# cart.net
KiCad netlist of a schematic drawn in EAGLE
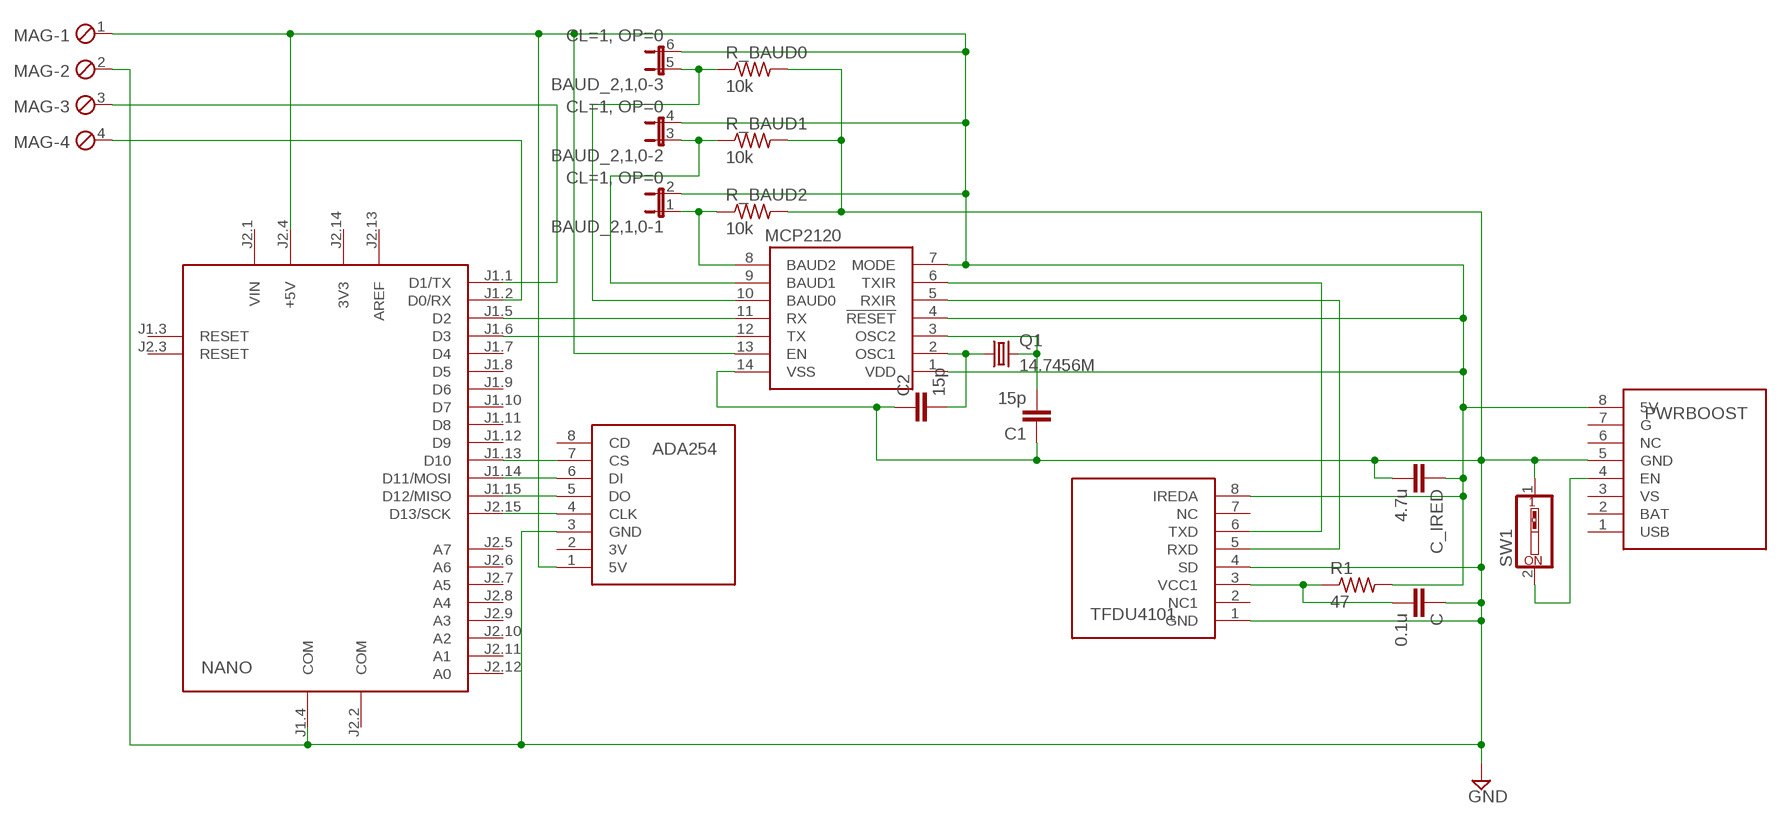
[diagram p0: schematic, sheet 1]

(export (version "E")
  (design (tool "Eeschema 10.0.6"))
  (components
    (comp (ref "ADA254")
      (value "ADA254_SD_READER")
      (footprint "eagle-import:ADA254_SD_READER")
      (libsource (lib "eagle-import") (part "ADA254_SD_READER"))
    )
    (comp (ref "BAUD_2,1,0")
      (value "CL=1, OP=0")
      (footprint "eagle-import:JP3Q")
      (libsource (lib "eagle-import") (part "JP3QE"))
    )
    (comp (ref "C")
      (value "0.1u")
      (footprint "eagle-import:C1206")
      (libsource (lib "eagle-import") (part "C-EUC1206"))
    )
    (comp (ref "C1")
      (value "15p")
      (footprint "eagle-import:C1206")
      (libsource (lib "eagle-import") (part "C-EUC1206"))
    )
    (comp (ref "C2")
      (value "15p")
      (footprint "eagle-import:C1206")
      (libsource (lib "eagle-import") (part "C-EUC1206"))
    )
    (comp (ref "C_IRED")
      (value "4.7u")
      (footprint "eagle-import:C1206")
      (libsource (lib "eagle-import") (part "C-EUC1206"))
    )
    (comp (ref "MAG")
      (value "MPT4")
      (footprint "eagle-import:4POL254")
      (libsource (lib "eagle-import") (part "MPT4"))
    )
    (comp (ref "MCP2120")
      (value "MCP2120_SOIC")
      (footprint "eagle-import:SO14")
      (libsource (lib "eagle-import") (part "MCP2120_SOIC"))
    )
    (comp (ref "NANO")
      (value "ARDUINO_NANO2")
      (footprint "eagle-import:ARDUINO_NANO2")
      (libsource (lib "eagle-import") (part "ARDUINO_NANO2"))
    )
    (comp (ref "PWRBOOST")
      (value "POWERBOOST_1000C")
      (footprint "eagle-import:POWERBOOST_1000C")
      (libsource (lib "eagle-import") (part "POWERBOOST_1000C"))
    )
    (comp (ref "Q1")
      (value "14.7456M")
      (footprint "eagle-import:TC26V")
      (libsource (lib "eagle-import") (part "CRYSTALTC26V"))
    )
    (comp (ref "R1")
      (value "47")
      (footprint "eagle-import:R1206W")
      (libsource (lib "eagle-import") (part "R-US_R1206W"))
    )
    (comp (ref "R_BAUD0")
      (value "10k")
      (footprint "eagle-import:R1206W")
      (libsource (lib "eagle-import") (part "R-US_R1206W"))
    )
    (comp (ref "R_BAUD1")
      (value "10k")
      (footprint "eagle-import:R1206W")
      (libsource (lib "eagle-import") (part "R-US_R1206W"))
    )
    (comp (ref "R_BAUD2")
      (value "10k")
      (footprint "eagle-import:R1206W")
      (libsource (lib "eagle-import") (part "R-US_R1206W"))
    )
    (comp (ref "SW1")
      (value "SW_DIP-1")
      (footprint "eagle-import:EDG-01")
      (libsource (lib "eagle-import") (part "SW_DIP-1"))
    )
    (comp (ref "TFDU4101")
      (value "TFDU4101_SIDE")
      (footprint "eagle-import:TFDU4101_SIDE")
      (libsource (lib "eagle-import") (part "TFDU4101_SIDE"))
    )
  )
  (nets
    (net (code "1") (name "/3V3") (class "Default")
      (node (ref "NANO") (pin "J2.14") (pinfunction "3V3_J2.14") (pintype "power_in"))
    )
    (net (code "2") (name "/AREF") (class "Default")
      (node (ref "NANO") (pin "J2.13") (pinfunction "AREF_J2.13") (pintype "power_in"))
    )
    (net (code "3") (name "/COM") (class "Default")
      (node (ref "NANO") (pin "J2.2") (pinfunction "COM_J2.2") (pintype "power_in"))
    )
    (net (code "4") (name "/VIN") (class "Default")
      (node (ref "NANO") (pin "J2.1") (pinfunction "VIN_J2.1") (pintype "power_in"))
    )
    (net (code "5") (name "GND") (class "Default")
      (node (ref "ADA254") (pin "3") (pinfunction "GND_3") (pintype "bidirectional"))
      (node (ref "C") (pin "1") (pinfunction "1_1") (pintype "passive"))
      (node (ref "C1") (pin "1") (pinfunction "1_1") (pintype "passive"))
      (node (ref "C2") (pin "1") (pinfunction "1_1") (pintype "passive"))
      (node (ref "C_IRED") (pin "2") (pinfunction "2_2") (pintype "passive"))
      (node (ref "MAG") (pin "2") (pinfunction "1_2") (pintype "passive"))
      (node (ref "MCP2120") (pin "14") (pinfunction "VSS_14") (pintype "bidirectional"))
      (node (ref "NANO") (pin "J1.4") (pinfunction "COM_J1.4") (pintype "power_in"))
      (node (ref "PWRBOOST") (pin "5") (pinfunction "GND_5") (pintype "bidirectional"))
      (node (ref "R_BAUD0") (pin "2") (pinfunction "2_2") (pintype "passive"))
      (node (ref "R_BAUD1") (pin "2") (pinfunction "2_2") (pintype "passive"))
      (node (ref "R_BAUD2") (pin "2") (pinfunction "2_2") (pintype "passive"))
      (node (ref "SW1") (pin "1") (pinfunction "1_1") (pintype "passive"))
      (node (ref "TFDU4101") (pin "1") (pinfunction "GND_1") (pintype "bidirectional"))
      (node (ref "TFDU4101") (pin "4") (pinfunction "SD_4") (pintype "bidirectional"))
    )
    (net (code "6") (name "Net-(ADA254-5V)") (class "Default")
      (node (ref "ADA254") (pin "1") (pinfunction "5V_1") (pintype "bidirectional"))
      (node (ref "BAUD_2,1,0") (pin "2") (pinfunction "2_2") (pintype "passive"))
      (node (ref "BAUD_2,1,0") (pin "4") (pinfunction "2_4") (pintype "passive"))
      (node (ref "BAUD_2,1,0") (pin "6") (pinfunction "2_6") (pintype "passive"))
      (node (ref "C_IRED") (pin "1") (pinfunction "1_1") (pintype "passive"))
      (node (ref "MAG") (pin "1") (pinfunction "1_1") (pintype "passive"))
      (node (ref "MCP2120") (pin "1") (pinfunction "VDD_1") (pintype "bidirectional"))
      (node (ref "MCP2120") (pin "13") (pinfunction "EN_13") (pintype "bidirectional"))
      (node (ref "MCP2120") (pin "4") (pinfunction "~{RESET}_4") (pintype "bidirectional"))
      (node (ref "MCP2120") (pin "7") (pinfunction "MODE_7") (pintype "bidirectional"))
      (node (ref "NANO") (pin "J2.4") (pinfunction "+5V_J2.4") (pintype "power_in"))
      (node (ref "PWRBOOST") (pin "8") (pinfunction "5V_8") (pintype "bidirectional"))
      (node (ref "R1") (pin "2") (pinfunction "2_2") (pintype "passive"))
      (node (ref "TFDU4101") (pin "8") (pinfunction "IREDA_8") (pintype "bidirectional"))
    )
    (net (code "7") (name "Net-(ADA254-CLK)") (class "Default")
      (node (ref "ADA254") (pin "4") (pinfunction "CLK_4") (pintype "bidirectional"))
      (node (ref "NANO") (pin "J2.15") (pinfunction "D13/SCK_J2.15") (pintype "bidirectional"))
    )
    (net (code "8") (name "Net-(ADA254-CS)") (class "Default")
      (node (ref "ADA254") (pin "7") (pinfunction "CS_7") (pintype "bidirectional"))
      (node (ref "NANO") (pin "J1.13") (pinfunction "D10_J1.13") (pintype "bidirectional"))
    )
    (net (code "9") (name "Net-(ADA254-DI)") (class "Default")
      (node (ref "ADA254") (pin "6") (pinfunction "DI_6") (pintype "bidirectional"))
      (node (ref "NANO") (pin "J1.14") (pinfunction "D11/MOSI_J1.14") (pintype "bidirectional"))
    )
    (net (code "10") (name "Net-(ADA254-DO)") (class "Default")
      (node (ref "ADA254") (pin "5") (pinfunction "DO_5") (pintype "bidirectional"))
      (node (ref "NANO") (pin "J1.15") (pinfunction "D12/MISO_J1.15") (pintype "bidirectional"))
    )
    (net (code "11") (name "Net-(BAUD_2,1,0B-1)") (class "Default")
      (node (ref "BAUD_2,1,0") (pin "3") (pinfunction "1_3") (pintype "passive"))
      (node (ref "MCP2120") (pin "9") (pinfunction "BAUD1_9") (pintype "bidirectional"))
      (node (ref "R_BAUD1") (pin "1") (pinfunction "1_1") (pintype "passive"))
    )
    (net (code "12") (name "Net-(BAUD_2,1,0C-1)") (class "Default")
      (node (ref "BAUD_2,1,0") (pin "5") (pinfunction "1_5") (pintype "passive"))
      (node (ref "MCP2120") (pin "10") (pinfunction "BAUD0_10") (pintype "bidirectional"))
      (node (ref "R_BAUD0") (pin "1") (pinfunction "1_1") (pintype "passive"))
    )
    (net (code "13") (name "Net-(MAGC-1)") (class "Default")
      (node (ref "MAG") (pin "3") (pinfunction "1_3") (pintype "passive"))
      (node (ref "NANO") (pin "J1.1") (pinfunction "D1/TX_J1.1") (pintype "bidirectional"))
    )
    (net (code "14") (name "Net-(MAGD-1)") (class "Default")
      (node (ref "MAG") (pin "4") (pinfunction "1_4") (pintype "passive"))
      (node (ref "NANO") (pin "J1.2") (pinfunction "D0/RX_J1.2") (pintype "bidirectional"))
    )
    (net (code "15") (name "Net-(MCP2120-BAUD2)") (class "Default")
      (node (ref "BAUD_2,1,0") (pin "1") (pinfunction "1_1") (pintype "passive"))
      (node (ref "MCP2120") (pin "8") (pinfunction "BAUD2_8") (pintype "bidirectional"))
      (node (ref "R_BAUD2") (pin "1") (pinfunction "1_1") (pintype "passive"))
    )
    (net (code "16") (name "Net-(MCP2120-OSC1)") (class "Default")
      (node (ref "C2") (pin "2") (pinfunction "2_2") (pintype "passive"))
      (node (ref "MCP2120") (pin "2") (pinfunction "OSC1_2") (pintype "bidirectional"))
      (node (ref "Q1") (pin "1") (pinfunction "1_1") (pintype "passive"))
    )
    (net (code "17") (name "Net-(MCP2120-OSC2)") (class "Default")
      (node (ref "C1") (pin "2") (pinfunction "2_2") (pintype "passive"))
      (node (ref "MCP2120") (pin "3") (pinfunction "OSC2_3") (pintype "bidirectional"))
      (node (ref "Q1") (pin "2") (pinfunction "2_2") (pintype "passive"))
    )
    (net (code "18") (name "Net-(MCP2120-RX)") (class "Default")
      (node (ref "MCP2120") (pin "11") (pinfunction "RX_11") (pintype "bidirectional"))
      (node (ref "NANO") (pin "J1.5") (pinfunction "D2_J1.5") (pintype "bidirectional"))
    )
    (net (code "19") (name "Net-(MCP2120-RXIR)") (class "Default")
      (node (ref "MCP2120") (pin "5") (pinfunction "RXIR_5") (pintype "bidirectional"))
      (node (ref "TFDU4101") (pin "5") (pinfunction "RXD_5") (pintype "bidirectional"))
    )
    (net (code "20") (name "Net-(MCP2120-TX)") (class "Default")
      (node (ref "MCP2120") (pin "12") (pinfunction "TX_12") (pintype "bidirectional"))
      (node (ref "NANO") (pin "J1.6") (pinfunction "D3_J1.6") (pintype "bidirectional"))
    )
    (net (code "21") (name "Net-(MCP2120-TXIR)") (class "Default")
      (node (ref "MCP2120") (pin "6") (pinfunction "TXIR_6") (pintype "bidirectional"))
      (node (ref "TFDU4101") (pin "6") (pinfunction "TXD_6") (pintype "bidirectional"))
    )
    (net (code "22") (name "Net-(PWRBOOST-EN)") (class "Default")
      (node (ref "PWRBOOST") (pin "4") (pinfunction "EN_4") (pintype "bidirectional"))
      (node (ref "SW1") (pin "2") (pinfunction "2_2") (pintype "passive"))
    )
    (net (code "23") (name "Net-(TFDU4101-VCC1)") (class "Default")
      (node (ref "C") (pin "2") (pinfunction "2_2") (pintype "passive"))
      (node (ref "R1") (pin "1") (pinfunction "1_1") (pintype "passive"))
      (node (ref "TFDU4101") (pin "3") (pinfunction "VCC1_3") (pintype "bidirectional"))
    )
    (net (code "24") (name "unconnected-(ADA254-3V-Pad2)") (class "Default")
      (node (ref "ADA254") (pin "2") (pinfunction "3V_2") (pintype "bidirectional"))
    )
    (net (code "25") (name "unconnected-(ADA254-CD-Pad8)") (class "Default")
      (node (ref "ADA254") (pin "8") (pinfunction "CD_8") (pintype "bidirectional"))
    )
    (net (code "26") (name "unconnected-(NANO-A0-PadJ2.12)") (class "Default")
      (node (ref "NANO") (pin "J2.12") (pinfunction "A0_J2.12") (pintype "bidirectional"))
    )
    (net (code "27") (name "unconnected-(NANO-A1-PadJ2.11)") (class "Default")
      (node (ref "NANO") (pin "J2.11") (pinfunction "A1_J2.11") (pintype "bidirectional"))
    )
    (net (code "28") (name "unconnected-(NANO-A2-PadJ2.10)") (class "Default")
      (node (ref "NANO") (pin "J2.10") (pinfunction "A2_J2.10") (pintype "bidirectional"))
    )
    (net (code "29") (name "unconnected-(NANO-A3-PadJ2.9)") (class "Default")
      (node (ref "NANO") (pin "J2.9") (pinfunction "A3_J2.9") (pintype "bidirectional"))
    )
    (net (code "30") (name "unconnected-(NANO-A4-PadJ2.8)") (class "Default")
      (node (ref "NANO") (pin "J2.8") (pinfunction "A4_J2.8") (pintype "bidirectional"))
    )
    (net (code "31") (name "unconnected-(NANO-A5-PadJ2.7)") (class "Default")
      (node (ref "NANO") (pin "J2.7") (pinfunction "A5_J2.7") (pintype "bidirectional"))
    )
    (net (code "32") (name "unconnected-(NANO-A6-PadJ2.6)") (class "Default")
      (node (ref "NANO") (pin "J2.6") (pinfunction "A6_J2.6") (pintype "bidirectional"))
    )
    (net (code "33") (name "unconnected-(NANO-A7-PadJ2.5)") (class "Default")
      (node (ref "NANO") (pin "J2.5") (pinfunction "A7_J2.5") (pintype "bidirectional"))
    )
    (net (code "34") (name "unconnected-(NANO-D4-PadJ1.7)") (class "Default")
      (node (ref "NANO") (pin "J1.7") (pinfunction "D4_J1.7") (pintype "bidirectional"))
    )
    (net (code "35") (name "unconnected-(NANO-D5-PadJ1.8)") (class "Default")
      (node (ref "NANO") (pin "J1.8") (pinfunction "D5_J1.8") (pintype "bidirectional"))
    )
    (net (code "36") (name "unconnected-(NANO-D6-PadJ1.9)") (class "Default")
      (node (ref "NANO") (pin "J1.9") (pinfunction "D6_J1.9") (pintype "bidirectional"))
    )
    (net (code "37") (name "unconnected-(NANO-D7-PadJ1.10)") (class "Default")
      (node (ref "NANO") (pin "J1.10") (pinfunction "D7_J1.10") (pintype "bidirectional"))
    )
    (net (code "38") (name "unconnected-(NANO-D8-PadJ1.11)") (class "Default")
      (node (ref "NANO") (pin "J1.11") (pinfunction "D8_J1.11") (pintype "bidirectional"))
    )
    (net (code "39") (name "unconnected-(NANO-D9-PadJ1.12)") (class "Default")
      (node (ref "NANO") (pin "J1.12") (pinfunction "D9_J1.12") (pintype "bidirectional"))
    )
    (net (code "40") (name "unconnected-(NANO-RESET-PadJ1.3)") (class "Default")
      (node (ref "NANO") (pin "J1.3") (pinfunction "RESET_J1.3") (pintype "bidirectional"))
    )
    (net (code "41") (name "unconnected-(NANO-RESET-PadJ2.3)") (class "Default")
      (node (ref "NANO") (pin "J2.3") (pinfunction "RESET_J2.3") (pintype "bidirectional"))
    )
    (net (code "42") (name "unconnected-(PWRBOOST-BAT-Pad2)") (class "Default")
      (node (ref "PWRBOOST") (pin "2") (pinfunction "BAT_2") (pintype "bidirectional"))
    )
    (net (code "43") (name "unconnected-(PWRBOOST-G-Pad7)") (class "Default")
      (node (ref "PWRBOOST") (pin "7") (pinfunction "G_7") (pintype "bidirectional"))
    )
    (net (code "44") (name "unconnected-(PWRBOOST-NC-Pad6)") (class "Default")
      (node (ref "PWRBOOST") (pin "6") (pinfunction "NC_6") (pintype "bidirectional"))
    )
    (net (code "45") (name "unconnected-(PWRBOOST-USB-Pad1)") (class "Default")
      (node (ref "PWRBOOST") (pin "1") (pinfunction "USB_1") (pintype "bidirectional"))
    )
    (net (code "46") (name "unconnected-(PWRBOOST-VS-Pad3)") (class "Default")
      (node (ref "PWRBOOST") (pin "3") (pinfunction "VS_3") (pintype "bidirectional"))
    )
    (net (code "47") (name "unconnected-(TFDU4101-NC-Pad7)") (class "Default")
      (node (ref "TFDU4101") (pin "7") (pinfunction "NC_7") (pintype "bidirectional"))
    )
    (net (code "48") (name "unconnected-(TFDU4101-NC1-Pad2)") (class "Default")
      (node (ref "TFDU4101") (pin "2") (pinfunction "NC1_2") (pintype "bidirectional"))
    )
  )
)
